# PowerSplitterLarge.net
KiCad netlist of a schematic drawn in EAGLE
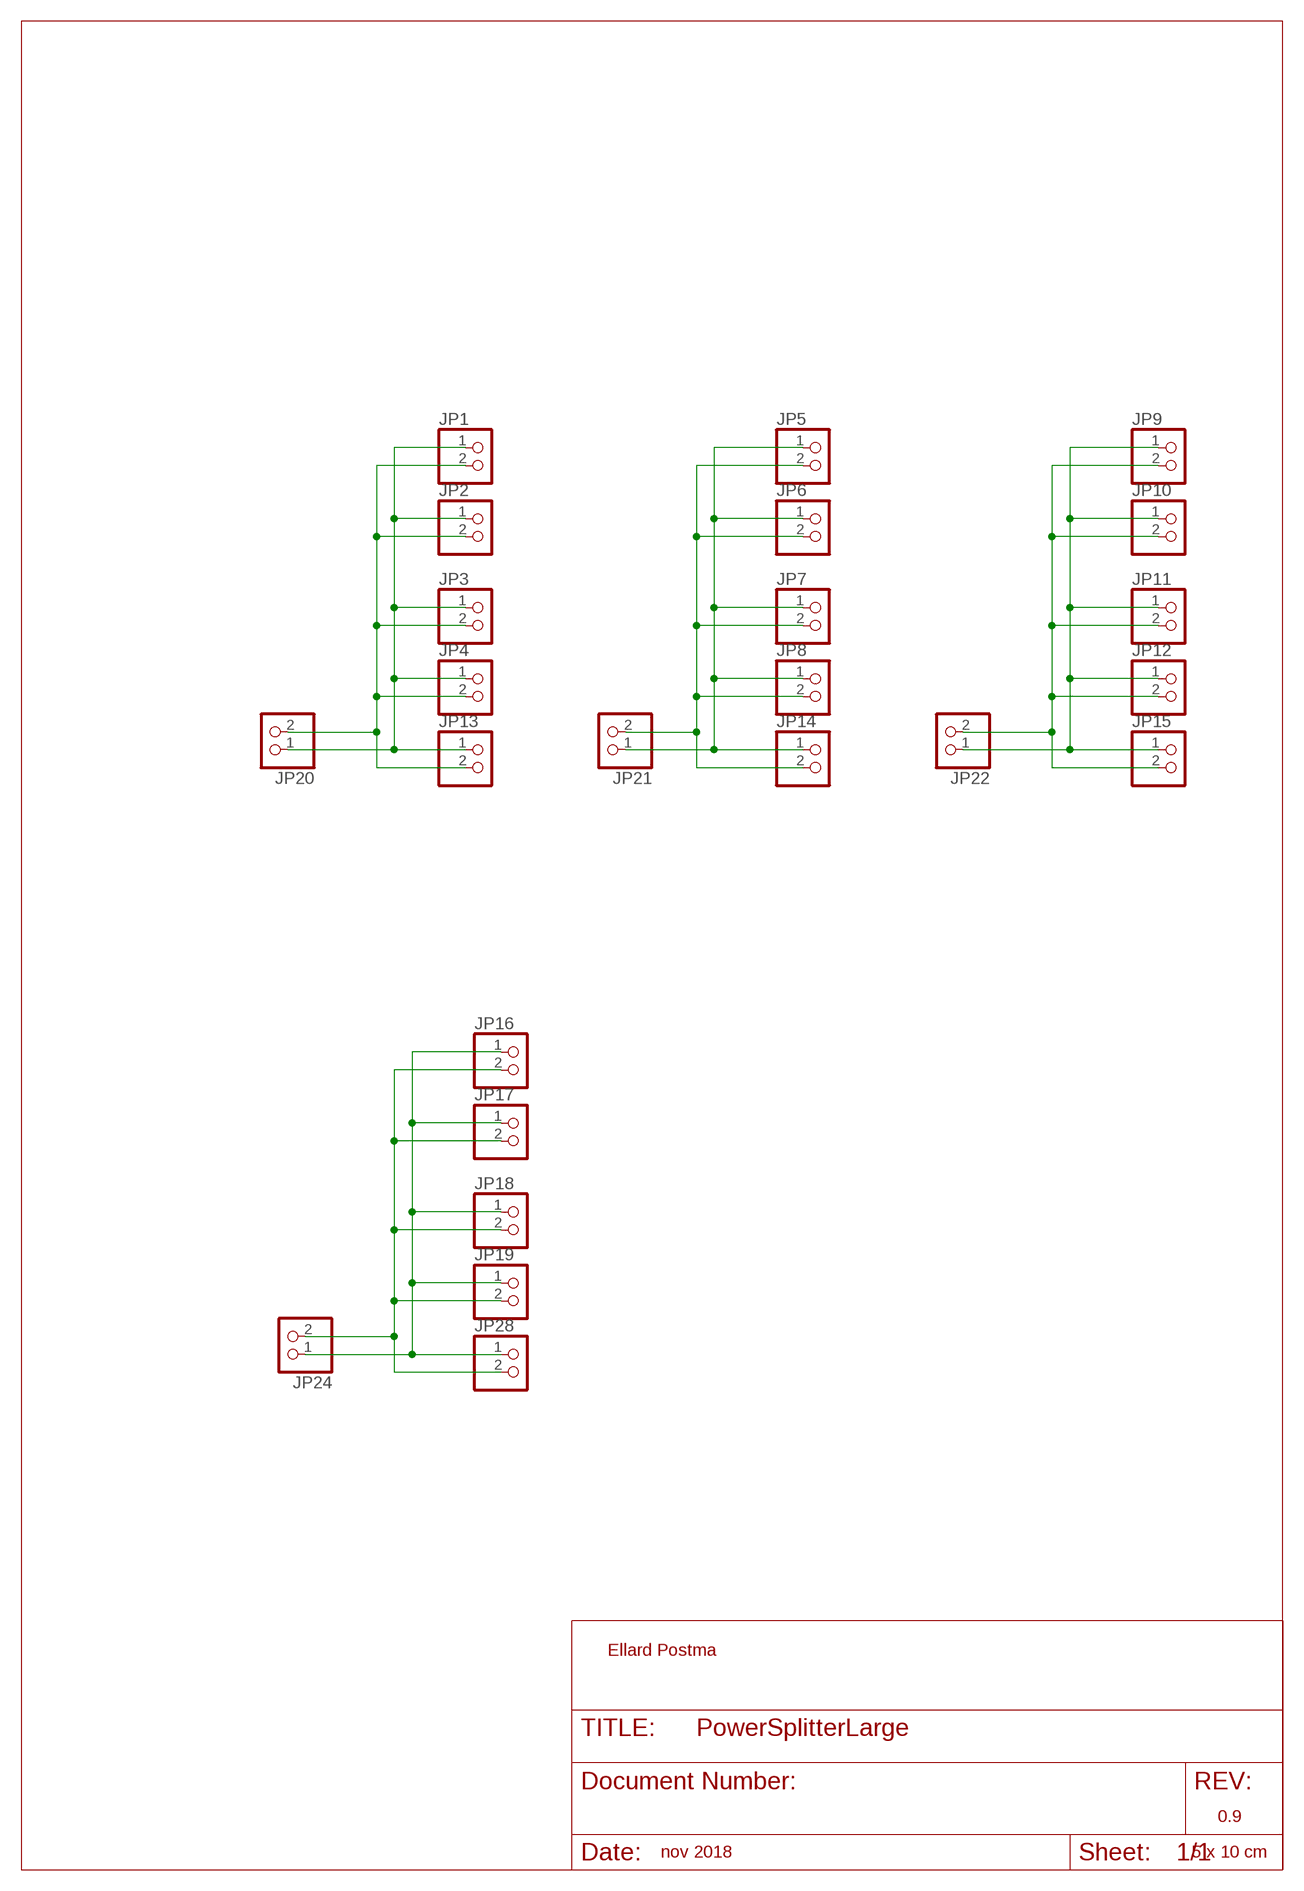
[diagram p0: schematic, sheet 1]

(export (version "E")
  (design (tool "Eeschema 10.0.6"))
  (components
    (comp (ref "JP1")
      (value "PINHD-1X2/90")
      (footprint "eagle-import:1X02_90")
      (libsource (lib "eagle-import") (part "PINHD-1X2/90"))
    )
    (comp (ref "JP2")
      (value "PINHD-1X2/90")
      (footprint "eagle-import:1X02_90")
      (libsource (lib "eagle-import") (part "PINHD-1X2/90"))
    )
    (comp (ref "JP3")
      (value "PINHD-1X2/90")
      (footprint "eagle-import:1X02_90")
      (libsource (lib "eagle-import") (part "PINHD-1X2/90"))
    )
    (comp (ref "JP4")
      (value "PINHD-1X2/90")
      (footprint "eagle-import:1X02_90")
      (libsource (lib "eagle-import") (part "PINHD-1X2/90"))
    )
    (comp (ref "JP5")
      (value "PINHD-1X2/90")
      (footprint "eagle-import:1X02_90")
      (libsource (lib "eagle-import") (part "PINHD-1X2/90"))
    )
    (comp (ref "JP6")
      (value "PINHD-1X2/90")
      (footprint "eagle-import:1X02_90")
      (libsource (lib "eagle-import") (part "PINHD-1X2/90"))
    )
    (comp (ref "JP7")
      (value "PINHD-1X2/90")
      (footprint "eagle-import:1X02_90")
      (libsource (lib "eagle-import") (part "PINHD-1X2/90"))
    )
    (comp (ref "JP8")
      (value "PINHD-1X2/90")
      (footprint "eagle-import:1X02_90")
      (libsource (lib "eagle-import") (part "PINHD-1X2/90"))
    )
    (comp (ref "JP9")
      (value "PINHD-1X2/90")
      (footprint "eagle-import:1X02_90")
      (libsource (lib "eagle-import") (part "PINHD-1X2/90"))
    )
    (comp (ref "JP10")
      (value "PINHD-1X2/90")
      (footprint "eagle-import:1X02_90")
      (libsource (lib "eagle-import") (part "PINHD-1X2/90"))
    )
    (comp (ref "JP11")
      (value "PINHD-1X2/90")
      (footprint "eagle-import:1X02_90")
      (libsource (lib "eagle-import") (part "PINHD-1X2/90"))
    )
    (comp (ref "JP12")
      (value "PINHD-1X2/90")
      (footprint "eagle-import:1X02_90")
      (libsource (lib "eagle-import") (part "PINHD-1X2/90"))
    )
    (comp (ref "JP13")
      (value "PINHD-1X2/90")
      (footprint "eagle-import:1X02_90")
      (libsource (lib "eagle-import") (part "PINHD-1X2/90"))
    )
    (comp (ref "JP14")
      (value "PINHD-1X2/90")
      (footprint "eagle-import:1X02_90")
      (libsource (lib "eagle-import") (part "PINHD-1X2/90"))
    )
    (comp (ref "JP15")
      (value "PINHD-1X2/90")
      (footprint "eagle-import:1X02_90")
      (libsource (lib "eagle-import") (part "PINHD-1X2/90"))
    )
    (comp (ref "JP16")
      (value "PINHD-1X2/90")
      (footprint "eagle-import:1X02_90")
      (libsource (lib "eagle-import") (part "PINHD-1X2/90"))
    )
    (comp (ref "JP17")
      (value "PINHD-1X2/90")
      (footprint "eagle-import:1X02_90")
      (libsource (lib "eagle-import") (part "PINHD-1X2/90"))
    )
    (comp (ref "JP18")
      (value "PINHD-1X2/90")
      (footprint "eagle-import:1X02_90")
      (libsource (lib "eagle-import") (part "PINHD-1X2/90"))
    )
    (comp (ref "JP19")
      (value "PINHD-1X2/90")
      (footprint "eagle-import:1X02_90")
      (libsource (lib "eagle-import") (part "PINHD-1X2/90"))
    )
    (comp (ref "JP20")
      (value "PINHD-1X2/90")
      (footprint "eagle-import:1X02_90")
      (libsource (lib "eagle-import") (part "pinhead_325_PINHD-1X2/90"))
    )
    (comp (ref "JP21")
      (value "PINHD-1X2/90")
      (footprint "eagle-import:1X02_90")
      (libsource (lib "eagle-import") (part "pinhead_325_PINHD-1X2/90"))
    )
    (comp (ref "JP22")
      (value "PINHD-1X2/90")
      (footprint "eagle-import:1X02_90")
      (libsource (lib "eagle-import") (part "pinhead_325_PINHD-1X2/90"))
    )
    (comp (ref "JP24")
      (value "PINHD-1X2/90")
      (footprint "eagle-import:1X02_90")
      (libsource (lib "eagle-import") (part "pinhead_325_PINHD-1X2/90"))
    )
    (comp (ref "JP28")
      (value "PINHD-1X2/90")
      (footprint "eagle-import:1X02_90")
      (libsource (lib "eagle-import") (part "PINHD-1X2/90"))
    )
  )
  (nets
    (net (code "1") (name "Net-(JP1-Pad1)") (class "Default")
      (node (ref "JP1") (pin "1") (pinfunction "1_1") (pintype "passive"))
      (node (ref "JP13") (pin "1") (pinfunction "1_1") (pintype "passive"))
      (node (ref "JP2") (pin "1") (pinfunction "1_1") (pintype "passive"))
      (node (ref "JP20") (pin "1") (pinfunction "1_1") (pintype "passive"))
      (node (ref "JP3") (pin "1") (pinfunction "1_1") (pintype "passive"))
      (node (ref "JP4") (pin "1") (pinfunction "1_1") (pintype "passive"))
    )
    (net (code "2") (name "Net-(JP1-Pad2)") (class "Default")
      (node (ref "JP1") (pin "2") (pinfunction "2_2") (pintype "passive"))
      (node (ref "JP13") (pin "2") (pinfunction "2_2") (pintype "passive"))
      (node (ref "JP2") (pin "2") (pinfunction "2_2") (pintype "passive"))
      (node (ref "JP20") (pin "2") (pinfunction "2_2") (pintype "passive"))
      (node (ref "JP3") (pin "2") (pinfunction "2_2") (pintype "passive"))
      (node (ref "JP4") (pin "2") (pinfunction "2_2") (pintype "passive"))
    )
    (net (code "3") (name "Net-(JP10-Pad1)") (class "Default")
      (node (ref "JP10") (pin "1") (pinfunction "1_1") (pintype "passive"))
      (node (ref "JP11") (pin "1") (pinfunction "1_1") (pintype "passive"))
      (node (ref "JP12") (pin "1") (pinfunction "1_1") (pintype "passive"))
      (node (ref "JP15") (pin "1") (pinfunction "1_1") (pintype "passive"))
      (node (ref "JP22") (pin "1") (pinfunction "1_1") (pintype "passive"))
      (node (ref "JP9") (pin "1") (pinfunction "1_1") (pintype "passive"))
    )
    (net (code "4") (name "Net-(JP10-Pad2)") (class "Default")
      (node (ref "JP10") (pin "2") (pinfunction "2_2") (pintype "passive"))
      (node (ref "JP11") (pin "2") (pinfunction "2_2") (pintype "passive"))
      (node (ref "JP12") (pin "2") (pinfunction "2_2") (pintype "passive"))
      (node (ref "JP15") (pin "2") (pinfunction "2_2") (pintype "passive"))
      (node (ref "JP22") (pin "2") (pinfunction "2_2") (pintype "passive"))
      (node (ref "JP9") (pin "2") (pinfunction "2_2") (pintype "passive"))
    )
    (net (code "5") (name "Net-(JP14-Pad1)") (class "Default")
      (node (ref "JP14") (pin "1") (pinfunction "1_1") (pintype "passive"))
      (node (ref "JP21") (pin "1") (pinfunction "1_1") (pintype "passive"))
      (node (ref "JP5") (pin "1") (pinfunction "1_1") (pintype "passive"))
      (node (ref "JP6") (pin "1") (pinfunction "1_1") (pintype "passive"))
      (node (ref "JP7") (pin "1") (pinfunction "1_1") (pintype "passive"))
      (node (ref "JP8") (pin "1") (pinfunction "1_1") (pintype "passive"))
    )
    (net (code "6") (name "Net-(JP14-Pad2)") (class "Default")
      (node (ref "JP14") (pin "2") (pinfunction "2_2") (pintype "passive"))
      (node (ref "JP21") (pin "2") (pinfunction "2_2") (pintype "passive"))
      (node (ref "JP5") (pin "2") (pinfunction "2_2") (pintype "passive"))
      (node (ref "JP6") (pin "2") (pinfunction "2_2") (pintype "passive"))
      (node (ref "JP7") (pin "2") (pinfunction "2_2") (pintype "passive"))
      (node (ref "JP8") (pin "2") (pinfunction "2_2") (pintype "passive"))
    )
    (net (code "7") (name "Net-(JP16-Pad1)") (class "Default")
      (node (ref "JP16") (pin "1") (pinfunction "1_1") (pintype "passive"))
      (node (ref "JP17") (pin "1") (pinfunction "1_1") (pintype "passive"))
      (node (ref "JP18") (pin "1") (pinfunction "1_1") (pintype "passive"))
      (node (ref "JP19") (pin "1") (pinfunction "1_1") (pintype "passive"))
      (node (ref "JP24") (pin "1") (pinfunction "1_1") (pintype "passive"))
      (node (ref "JP28") (pin "1") (pinfunction "1_1") (pintype "passive"))
    )
    (net (code "8") (name "Net-(JP16-Pad2)") (class "Default")
      (node (ref "JP16") (pin "2") (pinfunction "2_2") (pintype "passive"))
      (node (ref "JP17") (pin "2") (pinfunction "2_2") (pintype "passive"))
      (node (ref "JP18") (pin "2") (pinfunction "2_2") (pintype "passive"))
      (node (ref "JP19") (pin "2") (pinfunction "2_2") (pintype "passive"))
      (node (ref "JP24") (pin "2") (pinfunction "2_2") (pintype "passive"))
      (node (ref "JP28") (pin "2") (pinfunction "2_2") (pintype "passive"))
    )
  )
)
